# Memory.net
KiCad netlist of a schematic drawn in Altium Designer
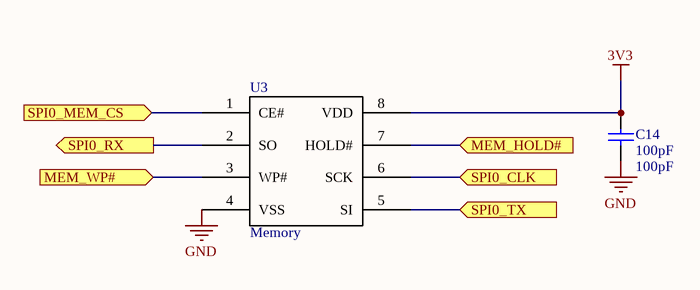
[diagram p0: Memory.SchDoc]

(export (version "E")
  (design (tool "Eeschema 10.0.6"))
  (components
    (comp (ref "C14")
      (value "100pF")
      (footprint "1608[0603]")
      (description "Capacitor (Semiconductor SIM Model)")
      (fields (field (name "ALTIUM_VALUE") "100pF") (field (name "PUBLISHER") "Altium Limited"))
      (libsource (lib "Miscellaneous Devices") (part "Cap Semi"))
    )
    (comp (ref "U3")
      (value "Memory")
      (footprint "SST25VF010A")
      (libsource (lib "LowPower_3ER_Parts") (part "SST25VF010A"))
    )
  )
  (nets
    (net (code "1") (name "/MEM_HOLD#") (class "Default")
      (node (ref "U3") (pin "7") (pinfunction "HOLD#_7") (pintype "passive"))
    )
    (net (code "2") (name "/MEM_WP#") (class "Default")
      (node (ref "U3") (pin "3") (pinfunction "WP#_3") (pintype "passive"))
    )
    (net (code "3") (name "/SPI0_CLK") (class "Default")
      (node (ref "U3") (pin "6") (pinfunction "SCK_6") (pintype "passive"))
    )
    (net (code "4") (name "/SPI0_MEM_CS") (class "Default")
      (node (ref "U3") (pin "1") (pinfunction "CE#_1") (pintype "passive"))
    )
    (net (code "5") (name "/SPI0_RX") (class "Default")
      (node (ref "U3") (pin "2") (pinfunction "SO_2") (pintype "passive"))
    )
    (net (code "6") (name "/SPI0_TX") (class "Default")
      (node (ref "U3") (pin "5") (pinfunction "SI_5") (pintype "passive"))
    )
    (net (code "7") (name "3V3") (class "Default")
      (node (ref "C14") (pin "2") (pinfunction "2_2") (pintype "passive"))
      (node (ref "U3") (pin "8") (pinfunction "VDD_8") (pintype "passive"))
    )
    (net (code "8") (name "GND") (class "Default")
      (node (ref "C14") (pin "1") (pinfunction "1_1") (pintype "passive"))
      (node (ref "U3") (pin "4") (pinfunction "VSS_4") (pintype "passive"))
    )
  )
)
